# LCD_Module.net
KiCad netlist of a schematic drawn in Altium Designer
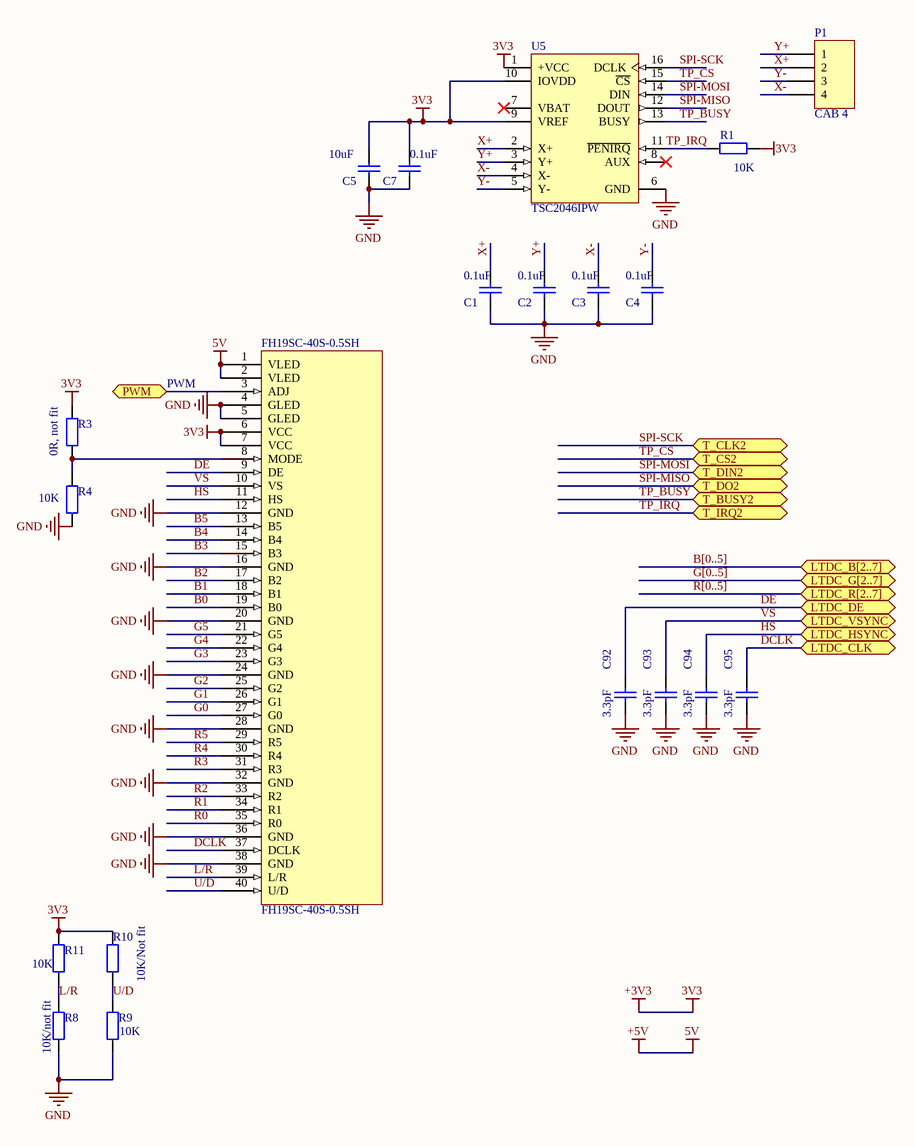
[diagram p0: LCD_Module.SchDoc]

(export (version "E")
  (design (tool "Eeschema 10.0.6"))
  (components
    (comp (ref "C1")
      (value "0.1uF")
      (footprint "0603_C")
      (description "Murata General Purpose Ceramic Cap 0603 2.2uF 10V 10% X7R")
      (libsource (lib "capacitor") (part "GRM188R71A225KE15"))
    )
    (comp (ref "C2")
      (value "0.1uF")
      (footprint "0603_C")
      (description "Murata General Purpose Ceramic Cap 0603 2.2uF 10V 10% X7R")
      (libsource (lib "capacitor") (part "GRM188R71A225KE15"))
    )
    (comp (ref "C3")
      (value "0.1uF")
      (footprint "0603_C")
      (description "Murata General Purpose Ceramic Cap 0603 2.2uF 10V 10% X7R")
      (libsource (lib "capacitor") (part "GRM188R71A225KE15"))
    )
    (comp (ref "C4")
      (value "0.1uF")
      (footprint "0603_C")
      (description "Murata General Purpose Ceramic Cap 0603 2.2uF 10V 10% X7R")
      (libsource (lib "capacitor") (part "GRM188R71A225KE15"))
    )
    (comp (ref "C5")
      (value "10uF")
      (footprint "0603_C")
      (description "Murata General Purpose Ceramic Cap 0603 2.2uF 10V 10% X7R")
      (libsource (lib "capacitor") (part "GRM188R71A225KE15"))
    )
    (comp (ref "C7")
      (value "0.1uF")
      (footprint "0603_C")
      (description "Murata General Purpose Ceramic Cap 0603 2.2uF 10V 10% X7R")
      (libsource (lib "capacitor") (part "GRM188R71A225KE15"))
    )
    (comp (ref "C92")
      (value "3.3pF")
      (footprint "0603_C")
      (description "Murata General Purpose Ceramic Cap 0603 2.2uF 10V 10% X7R")
      (libsource (lib "capacitor") (part "GRM188R71A225KE15"))
    )
    (comp (ref "C93")
      (value "3.3pF")
      (footprint "0603_C")
      (description "Murata General Purpose Ceramic Cap 0603 2.2uF 10V 10% X7R")
      (libsource (lib "capacitor") (part "GRM188R71A225KE15"))
    )
    (comp (ref "C94")
      (value "3.3pF")
      (footprint "0603_C")
      (description "Murata General Purpose Ceramic Cap 0603 2.2uF 10V 10% X7R")
      (libsource (lib "capacitor") (part "GRM188R71A225KE15"))
    )
    (comp (ref "C95")
      (value "3.3pF")
      (footprint "0603_C")
      (description "Murata General Purpose Ceramic Cap 0603 2.2uF 10V 10% X7R")
      (libsource (lib "capacitor") (part "GRM188R71A225KE15"))
    )
    (comp (ref "FH19SC-40S-0.5SH")
      (value "FH19SC-40S-0.5SH")
      (footprint "FFC/SM0.5-2H40A")
      (libsource (lib "lib_LCD_connector") (part "FH19SC-40S-0.5SH"))
    )
    (comp (ref "P1")
      (value "CAB 4")
      (footprint "FFC/SM1.0-2H4")
      (description "Header, 4-Pin")
      (fields (field (name "PUBLISHER") "Altium Limited"))
      (libsource (lib "Miscellaneous Connectors") (part "Header 4"))
    )
    (comp (ref "R1")
      (value "10K")
      (footprint "0603_R")
      (description "Yageo RES 10R 5% 1/10W 0603")
      (libsource (lib "") (part "RC0603JR-0710RL_1"))
    )
    (comp (ref "R3")
      (value "0R, not fit")
      (footprint "0603_R")
      (description "Yageo RES 10R 5% 1/10W 0603")
      (libsource (lib "") (part "RC0603JR-0710RL_2"))
    )
    (comp (ref "R4")
      (value "10K")
      (footprint "0603_R")
      (description "Yageo RES 10R 5% 1/10W 0603")
      (libsource (lib "") (part "RC0603JR-0710RL_2"))
    )
    (comp (ref "R8")
      (value "10K/not fit")
      (footprint "0603_R")
      (description "Yageo RES 10R 5% 1/10W 0603")
      (libsource (lib "resistor") (part "RC0603JR-0710RL"))
    )
    (comp (ref "R9")
      (value "10K")
      (footprint "0603_R")
      (description "Yageo RES 10R 5% 1/10W 0603")
      (libsource (lib "resistor") (part "RC0603JR-0710RL"))
    )
    (comp (ref "R10")
      (value "10K/Not fit")
      (footprint "0603_R")
      (description "Yageo RES 10R 5% 1/10W 0603")
      (libsource (lib "resistor") (part "RC0603JR-0710RL"))
    )
    (comp (ref "R11")
      (value "10K")
      (footprint "0603_R")
      (description "Yageo RES 10R 5% 1/10W 0603")
      (libsource (lib "resistor") (part "RC0603JR-0710RL"))
    )
    (comp (ref "U5")
      (value "TSC2046IPW")
      (footprint "PW016")
      (description "4-Wire Touch Screen controller with Low-Voltage I/O Interface, 16-Pin TSSOP, Pb-Free")
      (fields (field (name "PUBLISHER") "Altium Limited"))
      (libsource (lib "TI Interface Touch Screen Controller") (part "TSC2046IPW"))
    )
  )
  (nets
    (net (code "1") (name "+3V3") (class "Default")
      (node (ref "C5") (pin "1") (pinfunction "1_1") (pintype "passive"))
      (node (ref "C7") (pin "1") (pinfunction "1_1") (pintype "passive"))
      (node (ref "FH19SC-40S-0.5SH") (pin "6") (pinfunction "VCC_6") (pintype "power_in"))
      (node (ref "FH19SC-40S-0.5SH") (pin "7") (pinfunction "VCC_7") (pintype "power_in"))
      (node (ref "R1") (pin "1") (pinfunction "1_1") (pintype "passive"))
      (node (ref "R10") (pin "1") (pinfunction "1_1") (pintype "passive"))
      (node (ref "R11") (pin "1") (pinfunction "1_1") (pintype "passive"))
      (node (ref "R3") (pin "2") (pinfunction "2_2") (pintype "passive"))
      (node (ref "U5") (pin "1") (pinfunction "+VCC_1") (pintype "power_in"))
      (node (ref "U5") (pin "10") (pinfunction "IOVDD_10") (pintype "power_in"))
      (node (ref "U5") (pin "9") (pinfunction "VREF_9") (pintype "power_in"))
    )
    (net (code "2") (name "+5V") (class "Default")
      (node (ref "FH19SC-40S-0.5SH") (pin "1") (pinfunction "VLED_1") (pintype "power_in"))
      (node (ref "FH19SC-40S-0.5SH") (pin "2") (pinfunction "VLED_2") (pintype "power_in"))
    )
    (net (code "3") (name "/B0") (class "Default")
      (node (ref "FH19SC-40S-0.5SH") (pin "19") (pinfunction "B0_19") (pintype "input"))
    )
    (net (code "4") (name "/B1") (class "Default")
      (node (ref "FH19SC-40S-0.5SH") (pin "18") (pinfunction "B1_18") (pintype "input"))
    )
    (net (code "5") (name "/B2") (class "Default")
      (node (ref "FH19SC-40S-0.5SH") (pin "17") (pinfunction "B2_17") (pintype "input"))
    )
    (net (code "6") (name "/B3") (class "Default")
      (node (ref "FH19SC-40S-0.5SH") (pin "15") (pinfunction "B3_15") (pintype "input"))
    )
    (net (code "7") (name "/B4") (class "Default")
      (node (ref "FH19SC-40S-0.5SH") (pin "14") (pinfunction "B4_14") (pintype "input"))
    )
    (net (code "8") (name "/B5") (class "Default")
      (node (ref "FH19SC-40S-0.5SH") (pin "13") (pinfunction "B5_13") (pintype "input"))
    )
    (net (code "10") (name "/DCLK") (class "Default")
      (node (ref "C95") (pin "1") (pinfunction "1_1") (pintype "passive"))
      (node (ref "FH19SC-40S-0.5SH") (pin "37") (pinfunction "DCLK_37") (pintype "input"))
    )
    (net (code "11") (name "/DE") (class "Default")
      (node (ref "C92") (pin "1") (pinfunction "1_1") (pintype "passive"))
      (node (ref "FH19SC-40S-0.5SH") (pin "9") (pinfunction "DE_9") (pintype "input"))
    )
    (net (code "12") (name "/G0") (class "Default")
      (node (ref "FH19SC-40S-0.5SH") (pin "27") (pinfunction "G0_27") (pintype "input"))
    )
    (net (code "13") (name "/G1") (class "Default")
      (node (ref "FH19SC-40S-0.5SH") (pin "26") (pinfunction "G1_26") (pintype "input"))
    )
    (net (code "14") (name "/G2") (class "Default")
      (node (ref "FH19SC-40S-0.5SH") (pin "25") (pinfunction "G2_25") (pintype "input"))
    )
    (net (code "15") (name "/G3") (class "Default")
      (node (ref "FH19SC-40S-0.5SH") (pin "23") (pinfunction "G3_23") (pintype "input"))
    )
    (net (code "16") (name "/G4") (class "Default")
      (node (ref "FH19SC-40S-0.5SH") (pin "22") (pinfunction "G4_22") (pintype "input"))
    )
    (net (code "17") (name "/G5") (class "Default")
      (node (ref "FH19SC-40S-0.5SH") (pin "21") (pinfunction "G5_21") (pintype "input"))
    )
    (net (code "19") (name "/HS") (class "Default")
      (node (ref "C94") (pin "1") (pinfunction "1_1") (pintype "passive"))
      (node (ref "FH19SC-40S-0.5SH") (pin "11") (pinfunction "HS_11") (pintype "input"))
    )
    (net (code "20") (name "/L{slash}R") (class "Default")
      (node (ref "FH19SC-40S-0.5SH") (pin "39") (pinfunction "L/R_39") (pintype "input"))
      (node (ref "R11") (pin "2") (pinfunction "2_2") (pintype "passive"))
      (node (ref "R8") (pin "1") (pinfunction "1_1") (pintype "passive"))
    )
    (net (code "21") (name "/PWM") (class "Default")
      (node (ref "FH19SC-40S-0.5SH") (pin "3") (pinfunction "ADJ_3") (pintype "input"))
    )
    (net (code "22") (name "/R0") (class "Default")
      (node (ref "FH19SC-40S-0.5SH") (pin "35") (pinfunction "R0_35") (pintype "input"))
    )
    (net (code "23") (name "/R1") (class "Default")
      (node (ref "FH19SC-40S-0.5SH") (pin "34") (pinfunction "R1_34") (pintype "input"))
    )
    (net (code "24") (name "/R2") (class "Default")
      (node (ref "FH19SC-40S-0.5SH") (pin "33") (pinfunction "R2_33") (pintype "input"))
    )
    (net (code "25") (name "/R3") (class "Default")
      (node (ref "FH19SC-40S-0.5SH") (pin "31") (pinfunction "R3_31") (pintype "input"))
    )
    (net (code "26") (name "/R4") (class "Default")
      (node (ref "FH19SC-40S-0.5SH") (pin "30") (pinfunction "R4_30") (pintype "input"))
    )
    (net (code "27") (name "/R5") (class "Default")
      (node (ref "FH19SC-40S-0.5SH") (pin "29") (pinfunction "R5_29") (pintype "input"))
    )
    (net (code "29") (name "/SPI-MISO") (class "Default")
      (node (ref "U5") (pin "12") (pinfunction "DOUT_12") (pintype "output"))
    )
    (net (code "30") (name "/SPI-MOSI") (class "Default")
      (node (ref "U5") (pin "14") (pinfunction "DIN_14") (pintype "input"))
    )
    (net (code "31") (name "/SPI-SCK") (class "Default")
      (node (ref "U5") (pin "16") (pinfunction "DCLK_16") (pintype "input"))
    )
    (net (code "32") (name "/TP_BUSY") (class "Default")
      (node (ref "U5") (pin "13") (pinfunction "BUSY_13") (pintype "output"))
    )
    (net (code "33") (name "/TP_CS") (class "Default")
      (node (ref "U5") (pin "15") (pinfunction "~{CS}_15") (pintype "input"))
    )
    (net (code "34") (name "/TP_IRQ") (class "Default")
      (node (ref "R1") (pin "2") (pinfunction "2_2") (pintype "passive"))
      (node (ref "U5") (pin "11") (pinfunction "~{PENIRQ}_11") (pintype "input"))
    )
    (net (code "35") (name "/U{slash}D") (class "Default")
      (node (ref "FH19SC-40S-0.5SH") (pin "40") (pinfunction "U/D_40") (pintype "input"))
      (node (ref "R10") (pin "2") (pinfunction "2_2") (pintype "passive"))
      (node (ref "R9") (pin "1") (pinfunction "1_1") (pintype "passive"))
    )
    (net (code "36") (name "/VS") (class "Default")
      (node (ref "C93") (pin "1") (pinfunction "1_1") (pintype "passive"))
      (node (ref "FH19SC-40S-0.5SH") (pin "10") (pinfunction "VS_10") (pintype "input"))
    )
    (net (code "37") (name "/X+") (class "Default")
      (node (ref "C1") (pin "1") (pinfunction "1_1") (pintype "passive"))
      (node (ref "P1") (pin "2") (pinfunction "2_2") (pintype "passive"))
      (node (ref "U5") (pin "2") (pinfunction "X+_2") (pintype "input"))
    )
    (net (code "38") (name "/X-") (class "Default")
      (node (ref "C3") (pin "1") (pinfunction "1_1") (pintype "passive"))
      (node (ref "P1") (pin "4") (pinfunction "4_4") (pintype "passive"))
      (node (ref "U5") (pin "4") (pinfunction "X-_4") (pintype "input"))
    )
    (net (code "39") (name "/Y+") (class "Default")
      (node (ref "C2") (pin "1") (pinfunction "1_1") (pintype "passive"))
      (node (ref "P1") (pin "1") (pinfunction "1_1") (pintype "passive"))
      (node (ref "U5") (pin "3") (pinfunction "Y+_3") (pintype "input"))
    )
    (net (code "40") (name "/Y-") (class "Default")
      (node (ref "C4") (pin "1") (pinfunction "1_1") (pintype "passive"))
      (node (ref "P1") (pin "3") (pinfunction "3_3") (pintype "passive"))
      (node (ref "U5") (pin "5") (pinfunction "Y-_5") (pintype "input"))
    )
    (net (code "41") (name "GND") (class "Default")
      (node (ref "C1") (pin "2") (pinfunction "2_2") (pintype "passive"))
      (node (ref "C2") (pin "2") (pinfunction "2_2") (pintype "passive"))
      (node (ref "C3") (pin "2") (pinfunction "2_2") (pintype "passive"))
      (node (ref "C4") (pin "2") (pinfunction "2_2") (pintype "passive"))
      (node (ref "C5") (pin "2") (pinfunction "2_2") (pintype "passive"))
      (node (ref "C7") (pin "2") (pinfunction "2_2") (pintype "passive"))
      (node (ref "C92") (pin "2") (pinfunction "2_2") (pintype "passive"))
      (node (ref "C93") (pin "2") (pinfunction "2_2") (pintype "passive"))
      (node (ref "C94") (pin "2") (pinfunction "2_2") (pintype "passive"))
      (node (ref "C95") (pin "2") (pinfunction "2_2") (pintype "passive"))
      (node (ref "FH19SC-40S-0.5SH") (pin "12") (pinfunction "GND_12") (pintype "power_in"))
      (node (ref "FH19SC-40S-0.5SH") (pin "16") (pinfunction "GND_16") (pintype "power_in"))
      (node (ref "FH19SC-40S-0.5SH") (pin "20") (pinfunction "GND_20") (pintype "power_in"))
      (node (ref "FH19SC-40S-0.5SH") (pin "24") (pinfunction "GND_24") (pintype "power_in"))
      (node (ref "FH19SC-40S-0.5SH") (pin "28") (pinfunction "GND_28") (pintype "power_in"))
      (node (ref "FH19SC-40S-0.5SH") (pin "32") (pinfunction "GND_32") (pintype "power_in"))
      (node (ref "FH19SC-40S-0.5SH") (pin "36") (pinfunction "GND_36") (pintype "power_in"))
      (node (ref "FH19SC-40S-0.5SH") (pin "38") (pinfunction "GND_38") (pintype "power_in"))
      (node (ref "FH19SC-40S-0.5SH") (pin "4") (pinfunction "GLED_4") (pintype "power_in"))
      (node (ref "FH19SC-40S-0.5SH") (pin "5") (pinfunction "GLED_5") (pintype "power_in"))
      (node (ref "R4") (pin "1") (pinfunction "1_1") (pintype "passive"))
      (node (ref "R8") (pin "2") (pinfunction "2_2") (pintype "passive"))
      (node (ref "R9") (pin "2") (pinfunction "2_2") (pintype "passive"))
      (node (ref "U5") (pin "6") (pinfunction "GND_6") (pintype "power_in"))
    )
    (net (code "42") (name "Net-(FH19SC-40S-0.5SH-MODE)") (class "Default")
      (node (ref "FH19SC-40S-0.5SH") (pin "8") (pinfunction "MODE_8") (pintype "input"))
      (node (ref "R3") (pin "1") (pinfunction "1_1") (pintype "passive"))
      (node (ref "R4") (pin "2") (pinfunction "2_2") (pintype "passive"))
    )
    (net (code "43") (name "unconnected-(U5-AUX-Pad8)") (class "Default")
      (node (ref "U5") (pin "8") (pinfunction "AUX_8") (pintype "input+no_connect"))
    )
    (net (code "44") (name "unconnected-(U5-VBAT-Pad7)") (class "Default")
      (node (ref "U5") (pin "7") (pinfunction "VBAT_7") (pintype "power_in+no_connect"))
    )
  )
)
